# try_container3_1.net
KiCad netlist of a schematic drawn in EAGLE
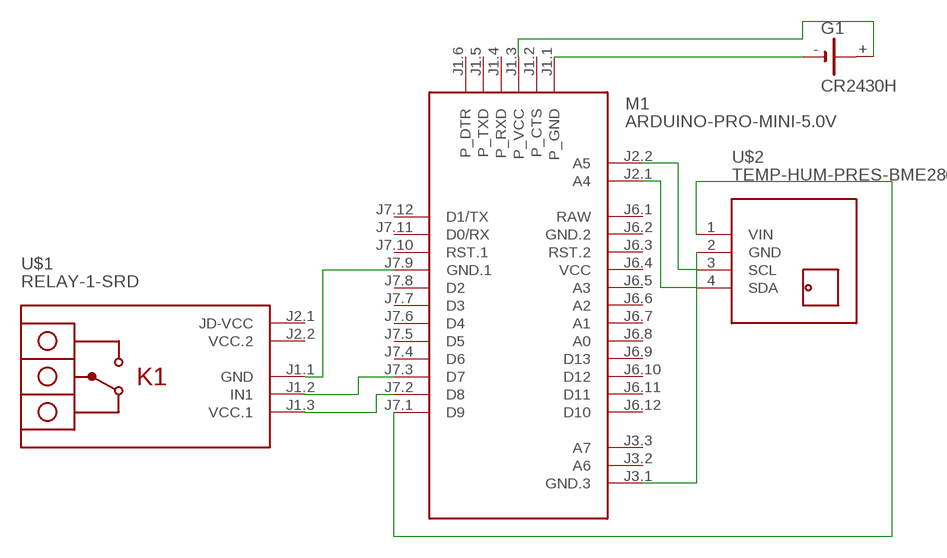
[diagram p0: schematic, sheet 1]

(export (version "E")
  (design (tool "Eeschema 10.0.6"))
  (components
    (comp (ref "G1")
      (value "CR2430H")
      (footprint "eagle-import:CR2430H")
      (libsource (lib "eagle-import") (part "CR2430H"))
    )
    (comp (ref "M1")
      (value "ARDUINO-PRO-MINI-5.0V")
      (footprint "eagle-import:ARDUINO-PRO-MINI")
      (libsource (lib "eagle-import") (part "ARDUINO-PRO-MINI-5.0V"))
    )
    (comp (ref "U$1")
      (value "RELAY-1-SRD")
      (footprint "eagle-import:RELAY-1-SRD")
      (libsource (lib "eagle-import") (part "RELAY-1-SRD"))
    )
    (comp (ref "U$2")
      (value "TEMP-HUM-PRES-BME280")
      (footprint "eagle-import:TEMP-HUM-PRES-BME280")
      (libsource (lib "eagle-import") (part "TEMP-HUM-PRES-BME280"))
    )
  )
  (nets
    (net (code "1") (name "/GND.2") (class "Default")
      (node (ref "M1") (pin "J6.2") (pinfunction "GND.2_J6.2") (pintype "power_in"))
    )
    (net (code "2") (name "/RAW") (class "Default")
      (node (ref "M1") (pin "J6.1") (pinfunction "RAW_J6.1") (pintype "power_in"))
    )
    (net (code "3") (name "/VCC") (class "Default")
      (node (ref "M1") (pin "J6.4") (pinfunction "VCC_J6.4") (pintype "power_in"))
    )
    (net (code "4") (name "/VCC.2") (class "Default")
      (node (ref "U$1") (pin "J2.2") (pinfunction "VCC.2_J2.2") (pintype "power_in"))
    )
    (net (code "5") (name "Net-(M1-A4)") (class "Default")
      (node (ref "M1") (pin "J2.1") (pinfunction "A4_J2.1") (pintype "bidirectional"))
      (node (ref "U$2") (pin "4") (pinfunction "SDA_4") (pintype "bidirectional"))
    )
    (net (code "6") (name "Net-(M1-A5)") (class "Default")
      (node (ref "M1") (pin "J2.2") (pinfunction "A5_J2.2") (pintype "bidirectional"))
      (node (ref "U$2") (pin "3") (pinfunction "SCL_3") (pintype "bidirectional"))
    )
    (net (code "7") (name "Net-(M1-D7)") (class "Default")
      (node (ref "M1") (pin "J7.3") (pinfunction "D7_J7.3") (pintype "bidirectional"))
      (node (ref "U$1") (pin "J1.2") (pinfunction "IN1_J1.2") (pintype "bidirectional"))
    )
    (net (code "8") (name "Net-(M1-D8)") (class "Default")
      (node (ref "M1") (pin "J7.2") (pinfunction "D8_J7.2") (pintype "bidirectional"))
      (node (ref "U$1") (pin "J1.3") (pinfunction "VCC.1_J1.3") (pintype "power_in"))
    )
    (net (code "9") (name "Net-(M1-D9)") (class "Default")
      (node (ref "M1") (pin "J7.1") (pinfunction "D9_J7.1") (pintype "bidirectional"))
      (node (ref "U$2") (pin "1") (pinfunction "VIN_1") (pintype "power_in"))
    )
    (net (code "10") (name "Net-(M1-GND.1)") (class "Default")
      (node (ref "M1") (pin "J7.9") (pinfunction "GND.1_J7.9") (pintype "power_in"))
      (node (ref "U$1") (pin "J1.1") (pinfunction "GND_J1.1") (pintype "power_in"))
    )
    (net (code "11") (name "Net-(M1-GND.3)") (class "Default")
      (node (ref "M1") (pin "J3.1") (pinfunction "GND.3_J3.1") (pintype "bidirectional"))
      (node (ref "U$2") (pin "2") (pinfunction "GND_2") (pintype "power_in"))
    )
    (net (code "12") (name "Net-(M1-P_GND)") (class "Default")
      (node (ref "G1") (pin "-") (pinfunction "-_-") (pintype "passive"))
      (node (ref "M1") (pin "J1.1") (pinfunction "P_GND_J1.1") (pintype "bidirectional"))
    )
    (net (code "13") (name "Net-(M1-P_VCC)") (class "Default")
      (node (ref "G1") (pin "+") (pinfunction "+_+") (pintype "passive"))
      (node (ref "M1") (pin "J1.3") (pinfunction "P_VCC_J1.3") (pintype "bidirectional"))
    )
    (net (code "14") (name "unconnected-(G1-+-Pad+@1)") (class "Default")
      (node (ref "G1") (pin "+@1") (pinfunction "+_+@1") (pintype "passive"))
    )
    (net (code "15") (name "unconnected-(M1-A0-PadJ6.8)") (class "Default")
      (node (ref "M1") (pin "J6.8") (pinfunction "A0_J6.8") (pintype "bidirectional"))
    )
    (net (code "16") (name "unconnected-(M1-A1-PadJ6.7)") (class "Default")
      (node (ref "M1") (pin "J6.7") (pinfunction "A1_J6.7") (pintype "bidirectional"))
    )
    (net (code "17") (name "unconnected-(M1-A2-PadJ6.6)") (class "Default")
      (node (ref "M1") (pin "J6.6") (pinfunction "A2_J6.6") (pintype "bidirectional"))
    )
    (net (code "18") (name "unconnected-(M1-A3-PadJ6.5)") (class "Default")
      (node (ref "M1") (pin "J6.5") (pinfunction "A3_J6.5") (pintype "bidirectional"))
    )
    (net (code "19") (name "unconnected-(M1-A6-PadJ3.2)") (class "Default")
      (node (ref "M1") (pin "J3.2") (pinfunction "A6_J3.2") (pintype "bidirectional"))
    )
    (net (code "20") (name "unconnected-(M1-A7-PadJ3.3)") (class "Default")
      (node (ref "M1") (pin "J3.3") (pinfunction "A7_J3.3") (pintype "bidirectional"))
    )
    (net (code "21") (name "unconnected-(M1-D0{slash}RX-PadJ7.11)") (class "Default")
      (node (ref "M1") (pin "J7.11") (pinfunction "D0/RX_J7.11") (pintype "bidirectional"))
    )
    (net (code "22") (name "unconnected-(M1-D1{slash}TX-PadJ7.12)") (class "Default")
      (node (ref "M1") (pin "J7.12") (pinfunction "D1/TX_J7.12") (pintype "bidirectional"))
    )
    (net (code "23") (name "unconnected-(M1-D2-PadJ7.8)") (class "Default")
      (node (ref "M1") (pin "J7.8") (pinfunction "D2_J7.8") (pintype "bidirectional"))
    )
    (net (code "24") (name "unconnected-(M1-D3-PadJ7.7)") (class "Default")
      (node (ref "M1") (pin "J7.7") (pinfunction "D3_J7.7") (pintype "bidirectional"))
    )
    (net (code "25") (name "unconnected-(M1-D4-PadJ7.6)") (class "Default")
      (node (ref "M1") (pin "J7.6") (pinfunction "D4_J7.6") (pintype "bidirectional"))
    )
    (net (code "26") (name "unconnected-(M1-D5-PadJ7.5)") (class "Default")
      (node (ref "M1") (pin "J7.5") (pinfunction "D5_J7.5") (pintype "bidirectional"))
    )
    (net (code "27") (name "unconnected-(M1-D6-PadJ7.4)") (class "Default")
      (node (ref "M1") (pin "J7.4") (pinfunction "D6_J7.4") (pintype "bidirectional"))
    )
    (net (code "28") (name "unconnected-(M1-D10-PadJ6.12)") (class "Default")
      (node (ref "M1") (pin "J6.12") (pinfunction "D10_J6.12") (pintype "bidirectional"))
    )
    (net (code "29") (name "unconnected-(M1-D11-PadJ6.11)") (class "Default")
      (node (ref "M1") (pin "J6.11") (pinfunction "D11_J6.11") (pintype "bidirectional"))
    )
    (net (code "30") (name "unconnected-(M1-D12-PadJ6.10)") (class "Default")
      (node (ref "M1") (pin "J6.10") (pinfunction "D12_J6.10") (pintype "bidirectional"))
    )
    (net (code "31") (name "unconnected-(M1-D13-PadJ6.9)") (class "Default")
      (node (ref "M1") (pin "J6.9") (pinfunction "D13_J6.9") (pintype "bidirectional"))
    )
    (net (code "32") (name "unconnected-(M1-P_CTS-PadJ1.2)") (class "Default")
      (node (ref "M1") (pin "J1.2") (pinfunction "P_CTS_J1.2") (pintype "bidirectional"))
    )
    (net (code "33") (name "unconnected-(M1-P_DTR-PadJ1.6)") (class "Default")
      (node (ref "M1") (pin "J1.6") (pinfunction "P_DTR_J1.6") (pintype "bidirectional"))
    )
    (net (code "34") (name "unconnected-(M1-P_RXD-PadJ1.4)") (class "Default")
      (node (ref "M1") (pin "J1.4") (pinfunction "P_RXD_J1.4") (pintype "bidirectional"))
    )
    (net (code "35") (name "unconnected-(M1-P_TXD-PadJ1.5)") (class "Default")
      (node (ref "M1") (pin "J1.5") (pinfunction "P_TXD_J1.5") (pintype "bidirectional"))
    )
    (net (code "36") (name "unconnected-(M1-RST.1-PadJ7.10)") (class "Default")
      (node (ref "M1") (pin "J7.10") (pinfunction "RST.1_J7.10") (pintype "bidirectional"))
    )
    (net (code "37") (name "unconnected-(M1-RST.2-PadJ6.3)") (class "Default")
      (node (ref "M1") (pin "J6.3") (pinfunction "RST.2_J6.3") (pintype "bidirectional"))
    )
    (net (code "38") (name "unconnected-(U$1-JD-VCC-PadJ2.1)") (class "Default")
      (node (ref "U$1") (pin "J2.1") (pinfunction "JD-VCC_J2.1") (pintype "bidirectional"))
    )
  )
)
